# wifi.net
KiCad netlist of a schematic drawn in Altium Designer
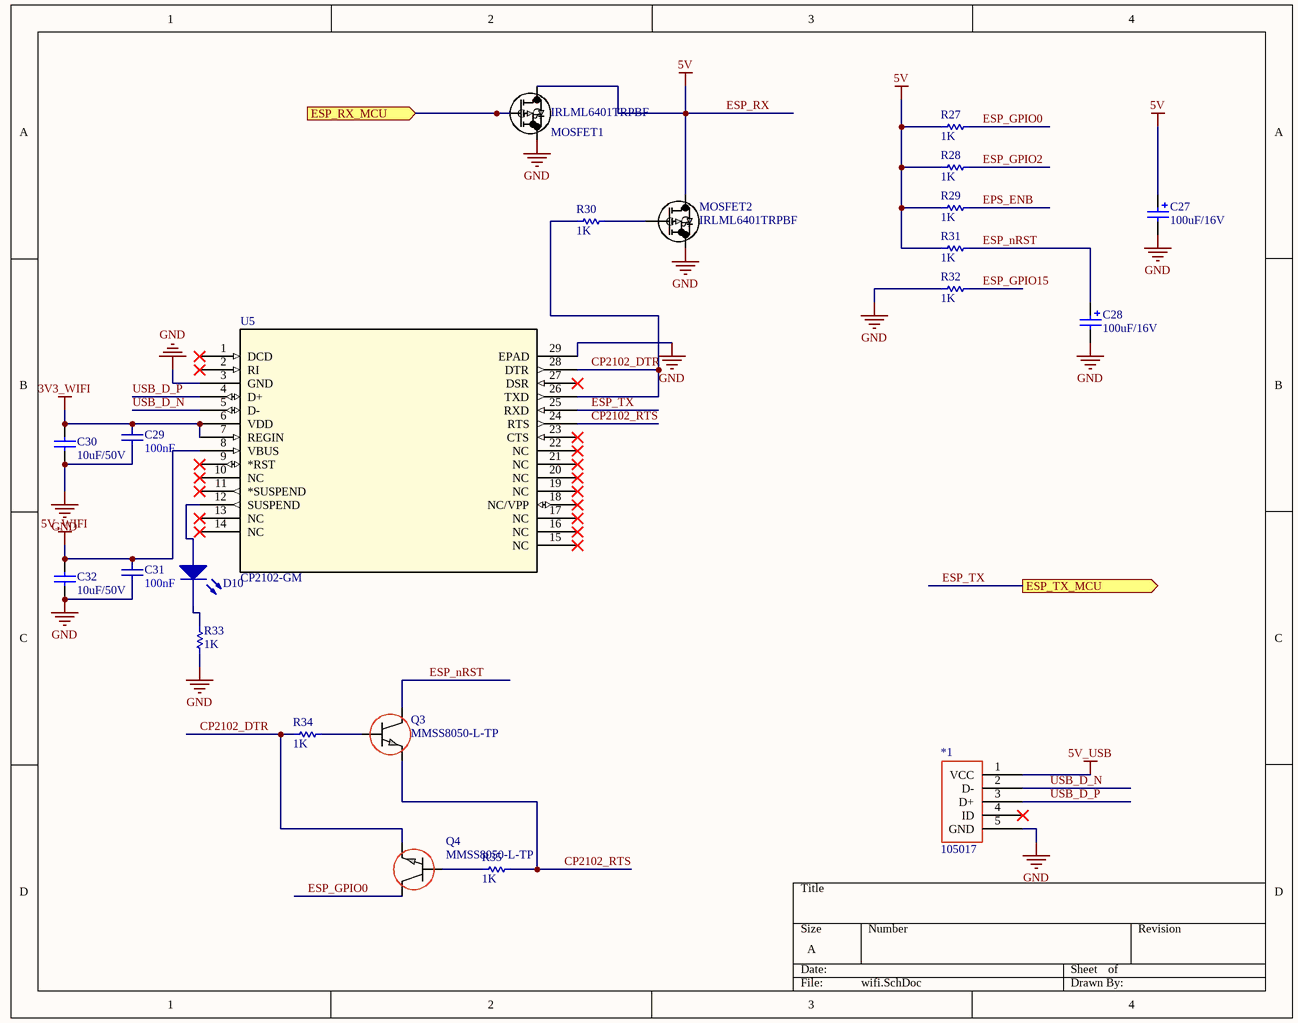
[diagram p0: wifi.SchDoc]

(export (version "E")
  (design (tool "Eeschema 10.0.6"))
  (components
    (comp (ref "*1")
      (value "105017")
      (footprint "CONN_105017-0001")
      (libsource (lib "INTERFACE-CP2102-GMR_QFN28_") (part "105017"))
    )
    (comp (ref "C27")
      (value "100uF/16V")
      (footprint "CAP_SM_TAN")
      (fields
        (field (name "MANUFACTURER") "Nichicon")
        (field (name "MANUFACTURER PART NUMBER") "UWX1C101MCL1GB")
        (field (name "Comment") "TAJB107M006RNJ")
      )
      (libsource (lib "Capacitor (1)") (part "Cap-Tan-100uF-16V"))
    )
    (comp (ref "C28")
      (value "100uF/16V")
      (footprint "CAP_SM_TAN")
      (fields
        (field (name "MANUFACTURER") "Nichicon")
        (field (name "MANUFACTURER PART NUMBER") "UWX1C101MCL1GB")
        (field (name "Comment") "TAJB107M006RNJ")
      )
      (libsource (lib "Capacitor (1)") (part "Cap-Tan-100uF-16V"))
    )
    (comp (ref "C29")
      (value "100nF")
      (footprint "CAP-SM-0805")
      (description "Capacitor")
      (fields (field (name "Comment") "Cap Non-Pol SMD"))
      (libsource (lib "PIF_C16_lib (1)") (part "Cap Non-Pol SMD"))
    )
    (comp (ref "C30")
      (value "10uF/50V")
      (footprint "CAP-SM-0805")
      (description "CAP CER 10UF 50V X5R 0805")
      (fields
        (field (name "MANUFACTURER") "Yageo")
        (field (name "MANUFACTURER PART NUMBER") "CC0805KKX5R9BB106")
      )
      (libsource (lib "Capacitor (1)") (part "Cap-10uF-50V-0805"))
    )
    (comp (ref "C31")
      (value "100nF")
      (footprint "CAP-SM-0805")
      (description "Capacitor")
      (fields (field (name "Comment") "Cap Non-Pol SMD"))
      (libsource (lib "PIF_C16_lib (1)") (part "Cap Non-Pol SMD"))
    )
    (comp (ref "C32")
      (value "10uF/50V")
      (footprint "CAP-SM-0805")
      (description "CAP CER 10UF 50V X5R 0805")
      (fields
        (field (name "MANUFACTURER") "Yageo")
        (field (name "MANUFACTURER PART NUMBER") "CC0805KKX5R9BB106")
      )
      (libsource (lib "Capacitor (1)") (part "Cap-10uF-50V-0805"))
    )
    (comp (ref "D10")
      (value "LED")
      (footprint "LED_0805_Blue")
      (libsource (lib "PIF_C16_lib (1)") (part "LED"))
    )
    (comp (ref "MOSFET1")
      (value "IRLML6401TRPBF")
      (footprint "irlml6406")
      (description "No Description Available")
      (fields (field (name "COPYRIGHT") "Copyright (C) 2018 Accelerated Designs. All rights reserved"))
      (libsource (lib "2020-08-05_14-48-21") (part "IRLML6401TRPBF"))
    )
    (comp (ref "MOSFET2")
      (value "IRLML6401TRPBF")
      (footprint "irlml6406")
      (description "No Description Available")
      (fields (field (name "COPYRIGHT") "Copyright (C) 2018 Accelerated Designs. All rights reserved"))
      (libsource (lib "2020-08-05_14-48-21") (part "IRLML6401TRPBF"))
    )
    (comp (ref "Q3")
      (value "MMSS8050-L-TP")
      (footprint "MMSS8050:SOT-23_MCC")
      (description "No Description Available")
      (fields (field (name "COPYRIGHT") "Copyright (C) 2018 Accelerated Designs. All rights reserved"))
      (libsource (lib "MMSS8050") (part "MMSS8050-L-TP"))
    )
    (comp (ref "Q4")
      (value "MMSS8050-L-TP")
      (footprint "MMSS8050:SOT-23_MCC")
      (description "No Description Available")
      (fields (field (name "COPYRIGHT") "Copyright (C) 2018 Accelerated Designs. All rights reserved"))
      (libsource (lib "MMSS8050") (part "MMSS8050-L-TP"))
    )
    (comp (ref "R27")
      (value "1K")
      (footprint "RES-SM-0805")
      (fields (field (name "Comment") "Resistor 1/4W"))
      (libsource (lib "PIF_C16_lib (1)") (part "RES"))
    )
    (comp (ref "R28")
      (value "1K")
      (footprint "RES-SM-0805")
      (fields (field (name "Comment") "Resistor 1/4W"))
      (libsource (lib "PIF_C16_lib (1)") (part "RES"))
    )
    (comp (ref "R29")
      (value "1K")
      (footprint "RES-SM-0805")
      (fields (field (name "Comment") "Resistor 1/4W"))
      (libsource (lib "PIF_C16_lib (1)") (part "RES"))
    )
    (comp (ref "R30")
      (value "1K")
      (footprint "RES-SM-0805")
      (fields (field (name "Comment") "Resistor 1/4W"))
      (libsource (lib "PIF_C16_lib (1)") (part "RES"))
    )
    (comp (ref "R31")
      (value "1K")
      (footprint "RES-SM-0805")
      (fields (field (name "Comment") "Resistor 1/4W"))
      (libsource (lib "PIF_C16_lib (1)") (part "RES"))
    )
    (comp (ref "R32")
      (value "1K")
      (footprint "RES-SM-0805")
      (fields (field (name "Comment") "Resistor 1/4W"))
      (libsource (lib "PIF_C16_lib (1)") (part "RES"))
    )
    (comp (ref "R33")
      (value "1K")
      (footprint "RES-SM-0805")
      (fields (field (name "Comment") "Resistor 1/4W"))
      (libsource (lib "PIF_C16_lib (1)") (part "RES"))
    )
    (comp (ref "R34")
      (value "1K")
      (footprint "RES-SM-0805")
      (fields (field (name "Comment") "Resistor 1/4W"))
      (libsource (lib "PIF_C16_lib (1)") (part "RES"))
    )
    (comp (ref "R35")
      (value "1K")
      (footprint "RES-SM-0805")
      (fields (field (name "Comment") "Resistor 1/4W"))
      (libsource (lib "PIF_C16_lib (1)") (part "RES"))
    )
    (comp (ref "U5")
      (value "CP2102-GM")
      (footprint "QFN28_5X5_SIL")
      (description "No Description Available")
      (fields (field (name "COPYRIGHT") "Copyright (C) 2018 Accelerated Designs. All rights reserved"))
      (libsource (lib "llibraryiii") (part "CP2102-GM"))
    )
  )
  (nets
    (net (code "1") (name "/CP2102_DTR") (class "Default")
      (node (ref "Q4") (pin "2") (pinfunction "E_2") (pintype "passive"))
      (node (ref "R30") (pin "2") (pintype "passive"))
      (node (ref "R34") (pin "2") (pintype "passive"))
      (node (ref "U5") (pin "26") (pinfunction "TXD_26") (pintype "output"))
      (node (ref "U5") (pin "28") (pinfunction "DTR_28") (pintype "output"))
    )
    (net (code "2") (name "/CP2102_RTS") (class "Default")
      (node (ref "Q3") (pin "2") (pinfunction "E_2") (pintype "passive"))
      (node (ref "R35") (pin "1") (pintype "passive"))
      (node (ref "U5") (pin "24") (pinfunction "RTS_24") (pintype "output"))
    )
    (net (code "3") (name "/EPS_ENB") (class "Default") (node (ref "R29") (pin "2") (pintype "passive")))
    (net (code "4") (name "/ESP_GPIO0") (class "Default")
      (node (ref "Q4") (pin "3") (pinfunction "C_3") (pintype "passive"))
      (node (ref "R27") (pin "2") (pintype "passive"))
    )
    (net (code "5") (name "/ESP_GPIO2") (class "Default") (node (ref "R28") (pin "2") (pintype "passive")))
    (net (code "6") (name "/ESP_GPIO15") (class "Default") (node (ref "R32") (pin "2") (pintype "passive")))
    (net (code "7") (name "/ESP_RX_MCU") (class "Default")
      (node (ref "MOSFET1") (pin "1") (pinfunction "G_1") (pintype "passive"))
    )
    (net (code "8") (name "/ESP_TX") (class "Default")
      (node (ref "U5") (pin "25") (pinfunction "RXD_25") (pintype "input"))
    )
    (net (code "9") (name "/ESP_nRST") (class "Default")
      (node (ref "C28") (pin "1") (pinfunction "1_1") (pintype "passive"))
      (node (ref "Q3") (pin "3") (pinfunction "C_3") (pintype "passive"))
      (node (ref "R31") (pin "2") (pintype "passive"))
    )
    (net (code "10") (name "/USB_D_N") (class "Default")
      (node (ref "*1") (pin "2") (pinfunction "D-_2") (pintype "passive"))
      (node (ref "U5") (pin "5") (pinfunction "D-_5") (pintype "bidirectional"))
    )
    (net (code "11") (name "/USB_D_P") (class "Default")
      (node (ref "*1") (pin "3") (pinfunction "D+_3") (pintype "passive"))
      (node (ref "U5") (pin "4") (pinfunction "D+_4") (pintype "bidirectional"))
    )
    (net (code "12") (name "3V3_WIFI") (class "Default")
      (node (ref "C29") (pin "2") (pinfunction "2_2") (pintype "passive"))
      (node (ref "C30") (pin "2") (pinfunction "2_2") (pintype "passive"))
      (node (ref "U5") (pin "6") (pinfunction "VDD_6") (pintype "power_in"))
      (node (ref "U5") (pin "7") (pinfunction "REGIN_7") (pintype "input"))
    )
    (net (code "13") (name "5V") (class "Default")
      (node (ref "C27") (pin "1") (pinfunction "1_1") (pintype "passive"))
      (node (ref "MOSFET1") (pin "3") (pinfunction "D_3") (pintype "passive"))
      (node (ref "MOSFET2") (pin "3") (pinfunction "D_3") (pintype "passive"))
      (node (ref "R27") (pin "1") (pintype "passive"))
      (node (ref "R28") (pin "1") (pintype "passive"))
      (node (ref "R29") (pin "1") (pintype "passive"))
      (node (ref "R31") (pin "1") (pintype "passive"))
    )
    (net (code "14") (name "5V_USB") (class "Default")
      (node (ref "*1") (pin "1") (pinfunction "VCC_1") (pintype "passive"))
    )
    (net (code "15") (name "5V_WIFI") (class "Default")
      (node (ref "C31") (pin "2") (pinfunction "2_2") (pintype "passive"))
      (node (ref "C32") (pin "2") (pinfunction "2_2") (pintype "passive"))
      (node (ref "U5") (pin "8") (pinfunction "VBUS_8") (pintype "input"))
    )
    (net (code "16") (name "GND") (class "Default")
      (node (ref "*1") (pin "5") (pinfunction "GND_5") (pintype "passive"))
      (node (ref "C27") (pin "2") (pinfunction "2_2") (pintype "passive"))
      (node (ref "C28") (pin "2") (pinfunction "2_2") (pintype "passive"))
      (node (ref "C29") (pin "1") (pinfunction "1_1") (pintype "passive"))
      (node (ref "C30") (pin "1") (pinfunction "1_1") (pintype "passive"))
      (node (ref "C31") (pin "1") (pinfunction "1_1") (pintype "passive"))
      (node (ref "C32") (pin "1") (pinfunction "1_1") (pintype "passive"))
      (node (ref "MOSFET1") (pin "2") (pinfunction "S_2") (pintype "passive"))
      (node (ref "MOSFET2") (pin "2") (pinfunction "S_2") (pintype "passive"))
      (node (ref "R32") (pin "1") (pintype "passive"))
      (node (ref "R33") (pin "1") (pintype "passive"))
      (node (ref "U5") (pin "29") (pinfunction "EPAD_29") (pintype "passive"))
      (node (ref "U5") (pin "3") (pinfunction "GND_3") (pintype "power_in"))
    )
    (net (code "17") (name "Net-(D10-A)") (class "Default")
      (node (ref "D10") (pin "1") (pinfunction "A_1") (pintype "passive"))
      (node (ref "U5") (pin "12") (pinfunction "SUSPEND_12") (pintype "output"))
    )
    (net (code "18") (name "Net-(D10-K)") (class "Default")
      (node (ref "D10") (pin "2") (pinfunction "K_2") (pintype "passive"))
      (node (ref "R33") (pin "2") (pintype "passive"))
    )
    (net (code "19") (name "Net-(MOSFET2-G)") (class "Default")
      (node (ref "MOSFET2") (pin "1") (pinfunction "G_1") (pintype "passive"))
      (node (ref "R30") (pin "1") (pintype "passive"))
    )
    (net (code "20") (name "Net-(Q3-B)") (class "Default")
      (node (ref "Q3") (pin "1") (pinfunction "B_1") (pintype "passive"))
      (node (ref "R34") (pin "1") (pintype "passive"))
    )
    (net (code "21") (name "Net-(Q4-B)") (class "Default")
      (node (ref "Q4") (pin "1") (pinfunction "B_1") (pintype "passive"))
      (node (ref "R35") (pin "2") (pintype "passive"))
    )
    (net (code "22") (name "unconnected-(*1-ID-Pad4)") (class "Default")
      (node (ref "*1") (pin "4") (pinfunction "ID_4") (pintype "passive+no_connect"))
    )
    (net (code "23") (name "unconnected-(U5-*RST-Pad9)") (class "Default")
      (node (ref "U5") (pin "9") (pinfunction "*RST_9") (pintype "bidirectional+no_connect"))
    )
    (net (code "24") (name "unconnected-(U5-*SUSPEND-Pad11)") (class "Default")
      (node (ref "U5") (pin "11") (pinfunction "*SUSPEND_11") (pintype "output+no_connect"))
    )
    (net (code "25") (name "unconnected-(U5-CTS-Pad23)") (class "Default")
      (node (ref "U5") (pin "23") (pinfunction "CTS_23") (pintype "input+no_connect"))
    )
    (net (code "26") (name "unconnected-(U5-DCD-Pad1)") (class "Default")
      (node (ref "U5") (pin "1") (pinfunction "DCD_1") (pintype "input+no_connect"))
    )
    (net (code "27") (name "unconnected-(U5-DSR-Pad27)") (class "Default")
      (node (ref "U5") (pin "27") (pinfunction "DSR_27") (pintype "input+no_connect"))
    )
    (net (code "28") (name "unconnected-(U5-NC-Pad10)") (class "Default")
      (node (ref "U5") (pin "10") (pinfunction "NC_10") (pintype "passive+no_connect"))
    )
    (net (code "29") (name "unconnected-(U5-NC-Pad13)") (class "Default")
      (node (ref "U5") (pin "13") (pinfunction "NC_13") (pintype "passive+no_connect"))
    )
    (net (code "30") (name "unconnected-(U5-NC-Pad14)") (class "Default")
      (node (ref "U5") (pin "14") (pinfunction "NC_14") (pintype "passive+no_connect"))
    )
    (net (code "31") (name "unconnected-(U5-NC-Pad15)") (class "Default")
      (node (ref "U5") (pin "15") (pinfunction "NC_15") (pintype "passive+no_connect"))
    )
    (net (code "32") (name "unconnected-(U5-NC-Pad16)") (class "Default")
      (node (ref "U5") (pin "16") (pinfunction "NC_16") (pintype "passive+no_connect"))
    )
    (net (code "33") (name "unconnected-(U5-NC-Pad17)") (class "Default")
      (node (ref "U5") (pin "17") (pinfunction "NC_17") (pintype "passive+no_connect"))
    )
    (net (code "34") (name "unconnected-(U5-NC-Pad19)") (class "Default")
      (node (ref "U5") (pin "19") (pinfunction "NC_19") (pintype "passive+no_connect"))
    )
    (net (code "35") (name "unconnected-(U5-NC-Pad20)") (class "Default")
      (node (ref "U5") (pin "20") (pinfunction "NC_20") (pintype "passive+no_connect"))
    )
    (net (code "36") (name "unconnected-(U5-NC-Pad21)") (class "Default")
      (node (ref "U5") (pin "21") (pinfunction "NC_21") (pintype "passive+no_connect"))
    )
    (net (code "37") (name "unconnected-(U5-NC-Pad22)") (class "Default")
      (node (ref "U5") (pin "22") (pinfunction "NC_22") (pintype "passive+no_connect"))
    )
    (net (code "38") (name "unconnected-(U5-NC{slash}VPP-Pad18)") (class "Default")
      (node (ref "U5") (pin "18") (pinfunction "NC/VPP_18") (pintype "bidirectional+no_connect"))
    )
    (net (code "39") (name "unconnected-(U5-RI-Pad2)") (class "Default")
      (node (ref "U5") (pin "2") (pinfunction "RI_2") (pintype "input+no_connect"))
    )
  )
)
